# Keg_Cop_-_Daisy_Chain.net
KiCad netlist of a schematic drawn in EAGLE
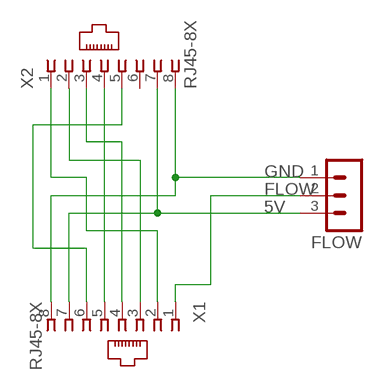
[diagram p0: schematic, sheet 1]

(export (version "E")
  (design (tool "Eeschema 10.0.6"))
  (components
    (comp (ref "FLOW")
      (value "HDR-3")
      (footprint "eagle-import:HDR-3_VERT")
      (libsource (lib "eagle-import") (part "HDR-3"))
    )
    (comp (ref "X1")
      (value "RJ45-8X")
      (footprint "eagle-import:RJ45-NO-SHIELD")
      (libsource (lib "eagle-import") (part "RJ45-8X"))
    )
    (comp (ref "X2")
      (value "RJ45-8X")
      (footprint "eagle-import:RJ45-NO-SHIELD")
      (libsource (lib "eagle-import") (part "RJ45-8X"))
    )
  )
  (nets
    (net (code "1") (name "/5V") (class "Default")
      (node (ref "FLOW") (pin "3") (pinfunction "3_3") (pintype "passive"))
      (node (ref "X1") (pin "7") (pinfunction "7_7") (pintype "passive"))
      (node (ref "X2") (pin "7") (pinfunction "7_7") (pintype "passive"))
    )
    (net (code "2") (name "/FLOW") (class "Default")
      (node (ref "FLOW") (pin "2") (pinfunction "2_2") (pintype "passive"))
      (node (ref "X1") (pin "1") (pinfunction "1_1") (pintype "passive"))
    )
    (net (code "3") (name "/GND") (class "Default")
      (node (ref "FLOW") (pin "1") (pinfunction "1_1") (pintype "passive"))
      (node (ref "X1") (pin "8") (pinfunction "8_8") (pintype "passive"))
      (node (ref "X2") (pin "8") (pinfunction "8_8") (pintype "passive"))
    )
    (net (code "4") (name "Net-(X1-Pad2)") (class "Default")
      (node (ref "X1") (pin "2") (pinfunction "2_2") (pintype "passive"))
      (node (ref "X2") (pin "1") (pinfunction "1_1") (pintype "passive"))
    )
    (net (code "5") (name "Net-(X1-Pad3)") (class "Default")
      (node (ref "X1") (pin "3") (pinfunction "3_3") (pintype "passive"))
      (node (ref "X2") (pin "2") (pinfunction "2_2") (pintype "passive"))
    )
    (net (code "6") (name "Net-(X1-Pad4)") (class "Default")
      (node (ref "X1") (pin "4") (pinfunction "4_4") (pintype "passive"))
      (node (ref "X2") (pin "3") (pinfunction "3_3") (pintype "passive"))
    )
    (net (code "7") (name "Net-(X1-Pad5)") (class "Default")
      (node (ref "X1") (pin "5") (pinfunction "5_5") (pintype "passive"))
      (node (ref "X2") (pin "4") (pinfunction "4_4") (pintype "passive"))
    )
    (net (code "8") (name "Net-(X1-Pad6)") (class "Default")
      (node (ref "X1") (pin "6") (pinfunction "6_6") (pintype "passive"))
      (node (ref "X2") (pin "5") (pinfunction "5_5") (pintype "passive"))
    )
    (net (code "9") (name "unconnected-(X2-Pad6)") (class "Default")
      (node (ref "X2") (pin "6") (pinfunction "6_6") (pintype "passive"))
    )
  )
)
